# B5PLMF_MAR_HF_B9.net
KiCad netlist of a schematic drawn in Altium Designer
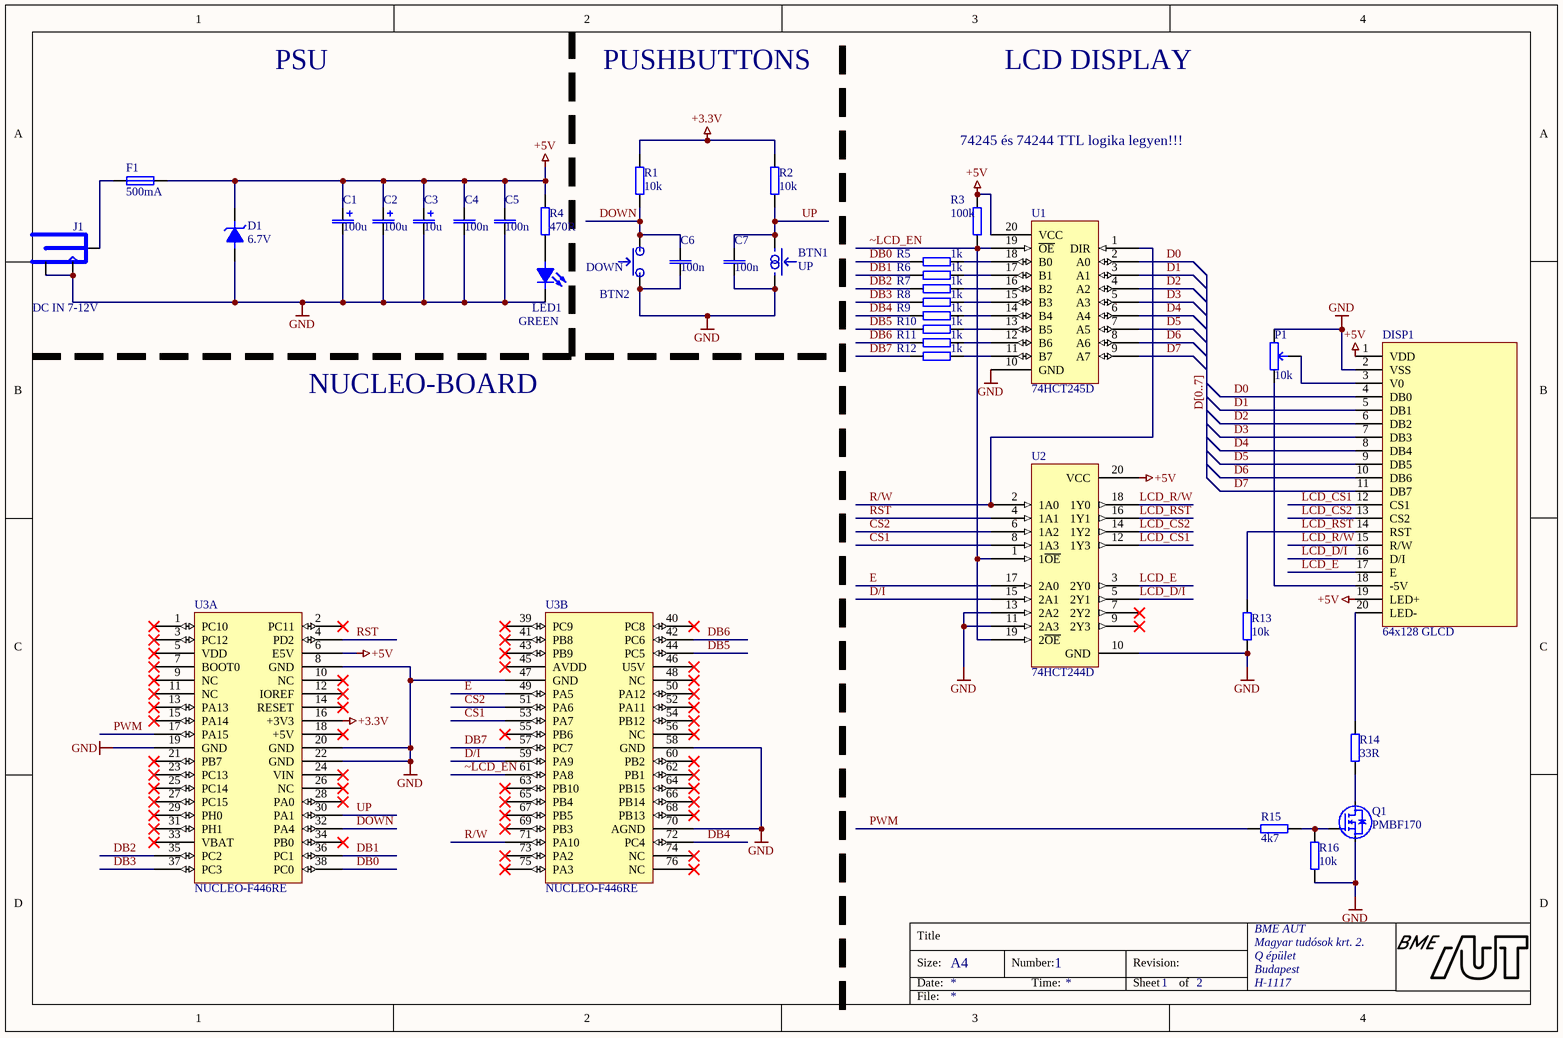
[diagram p0: B5PLMF_MAR_HF_B9.SchDoc]

(export (version "E")
  (design (tool "Eeschema 10.0.6"))
  (components
    (comp (ref "BTN1")
      (value "UP")
      (footprint "PBUTTON_SMD")
      (description "Tactile push button")
      (libsource (lib "SCH_LIB") (part "PUSHBUTTON"))
    )
    (comp (ref "BTN2")
      (value "DOWN")
      (footprint "PBUTTON_SMD")
      (description "Tactile push button")
      (libsource (lib "SCH_LIB") (part "PUSHBUTTON"))
    )
    (comp (ref "C1")
      (value "100u")
      (footprint "D8 ELKO")
      (description "POLARIZED CAPACITOR")
      (libsource (lib "SCH_LIB") (part "CAP_POL"))
    )
    (comp (ref "C2")
      (value "100u")
      (footprint "D8 ELKO")
      (description "POLARIZED CAPACITOR")
      (libsource (lib "SCH_LIB") (part "CAP_POL"))
    )
    (comp (ref "C3")
      (value "10u")
      (footprint "CAP 1210")
      (description "POLARIZED CAPACITOR")
      (libsource (lib "SCH_LIB") (part "CAP_POL"))
    )
    (comp (ref "C4")
      (value "100n")
      (footprint "CAP 0805")
      (description "NON POLARIZED CAPACITOR")
      (libsource (lib "SCH_LIB") (part "CAP"))
    )
    (comp (ref "C5")
      (value "100n")
      (footprint "CAP 0805")
      (description "NON POLARIZED CAPACITOR")
      (libsource (lib "SCH_LIB") (part "CAP"))
    )
    (comp (ref "C6")
      (value "100n")
      (footprint "CAP 0805")
      (description "NON POLARIZED CAPACITOR")
      (libsource (lib "SCH_LIB") (part "CAP"))
    )
    (comp (ref "C7")
      (value "100n")
      (footprint "CAP 0805")
      (description "NON POLARIZED CAPACITOR")
      (libsource (lib "SCH_LIB") (part "CAP"))
    )
    (comp (ref "D1")
      (value "6.7V")
      (footprint "DO-214AC")
      (description "SUPRESSOR DIODE")
      (libsource (lib "SCH_LIB") (part "SUPRESSOR DIODE"))
    )
    (comp (ref "DISP1")
      (value "64x128 GLCD")
      (footprint "64128Q")
      (description "64x128 pixel graphical LCD display from Displaytech")
      (libsource (lib "SCH_LIB") (part "64128QCCBW-3LP"))
    )
    (comp (ref "F1")
      (value "500mA")
      (footprint "FUSE1812")
      (description "FUSE")
      (libsource (lib "SCH_LIB") (part "FUSE"))
    )
    (comp (ref "J1")
      (value "DC IN 7-12V")
      (footprint "DC POWER CONNECTOR")
      (description "DC POWER CONNECTOR 5.5/2.1/9.5mm")
      (libsource (lib "SCH_LIB") (part "DC POWER CONN"))
    )
    (comp (ref "LED1")
      (value "GREEN")
      (footprint "LED 0805G")
      (description "LED")
      (libsource (lib "SCH_LIB") (part "LED"))
    )
    (comp (ref "P1")
      (value "10k")
      (footprint "PT10")
      (description "RESISTOR")
      (libsource (lib "SCH_LIB") (part "POT"))
    )
    (comp (ref "Q1")
      (value "PMBF170")
      (footprint "SOT23")
      (description "N-Channel MOSFET")
      (libsource (lib "SCH_LIB") (part "PMBF170"))
    )
    (comp (ref "R1")
      (value "10k")
      (footprint "RES 0805")
      (description "RESISTOR")
      (libsource (lib "") (part "RES_1"))
    )
    (comp (ref "R2")
      (value "10k")
      (footprint "RES 0805")
      (description "RESISTOR")
      (libsource (lib "") (part "RES_1"))
    )
    (comp (ref "R3")
      (value "100k")
      (footprint "RES 0805")
      (description "RESISTOR")
      (libsource (lib "") (part "RES_1"))
    )
    (comp (ref "R4")
      (value "470R")
      (footprint "RES 0805")
      (description "RESISTOR")
      (libsource (lib "") (part "RES_1"))
    )
    (comp (ref "R5")
      (value "1k")
      (footprint "RES 0805")
      (description "RESISTOR")
      (libsource (lib "SCH_LIB") (part "RES"))
    )
    (comp (ref "R6")
      (value "1k")
      (footprint "RES 0805")
      (description "RESISTOR")
      (libsource (lib "SCH_LIB") (part "RES"))
    )
    (comp (ref "R7")
      (value "1k")
      (footprint "RES 0805")
      (description "RESISTOR")
      (libsource (lib "SCH_LIB") (part "RES"))
    )
    (comp (ref "R8")
      (value "1k")
      (footprint "RES 0805")
      (description "RESISTOR")
      (libsource (lib "SCH_LIB") (part "RES"))
    )
    (comp (ref "R9")
      (value "1k")
      (footprint "RES 0805")
      (description "RESISTOR")
      (libsource (lib "SCH_LIB") (part "RES"))
    )
    (comp (ref "R10")
      (value "1k")
      (footprint "RES 0805")
      (description "RESISTOR")
      (libsource (lib "SCH_LIB") (part "RES"))
    )
    (comp (ref "R11")
      (value "1k")
      (footprint "RES 0805")
      (description "RESISTOR")
      (libsource (lib "SCH_LIB") (part "RES"))
    )
    (comp (ref "R12")
      (value "1k")
      (footprint "RES 0805")
      (description "RESISTOR")
      (libsource (lib "SCH_LIB") (part "RES"))
    )
    (comp (ref "R13")
      (value "10k")
      (footprint "RES 0805")
      (description "RESISTOR")
      (libsource (lib "") (part "RES_1"))
    )
    (comp (ref "R14")
      (value "33R")
      (footprint "RES 0805")
      (description "RESISTOR")
      (libsource (lib "") (part "RES_1"))
    )
    (comp (ref "R15")
      (value "4k7")
      (footprint "RES 0805")
      (description "RESISTOR")
      (libsource (lib "SCH_LIB") (part "RES"))
    )
    (comp (ref "R16")
      (value "10k")
      (footprint "RES 0805")
      (description "RESISTOR")
      (libsource (lib "") (part "RES_1"))
    )
    (comp (ref "U1")
      (value "74HCT245D")
      (footprint "SO20")
      (description "8x Bidirectional bus transciever")
      (libsource (lib "SCH_LIB") (part "74HCT245"))
    )
    (comp (ref "U2")
      (value "74HCT244D")
      (footprint "SO20")
      (description "8xBuffer/Line Driver")
      (libsource (lib "SCH_LIB") (part "74HCT244D"))
    )
    (comp (ref "U3")
      (value "NUCLEO-F446RE")
      (footprint "STM32F4xx_Nucleo")
      (description "STM32F4xx Nucleo board")
      (libsource (lib "SCH_LIB") (part "NUCLEO-F446RE"))
    )
  )
  (nets
    (net (code "1") (name "+3.3V") (class "Default")
      (node (ref "R1") (pin "2") (pinfunction "2_2") (pintype "passive"))
      (node (ref "R2") (pin "2") (pinfunction "2_2") (pintype "passive"))
      (node (ref "U3") (pin "16") (pinfunction "+3V3_16") (pintype "power_in"))
    )
    (net (code "2") (name "+5V") (class "Default")
      (node (ref "C1") (pin "1") (pinfunction "+_1") (pintype "passive"))
      (node (ref "C2") (pin "1") (pinfunction "+_1") (pintype "passive"))
      (node (ref "C3") (pin "1") (pinfunction "+_1") (pintype "passive"))
      (node (ref "C4") (pin "2") (pinfunction "2_2") (pintype "passive"))
      (node (ref "C5") (pin "2") (pinfunction "2_2") (pintype "passive"))
      (node (ref "D1") (pin "2") (pinfunction "K_2") (pintype "passive"))
      (node (ref "DISP1") (pin "1") (pinfunction "VDD_1") (pintype "passive"))
      (node (ref "DISP1") (pin "19") (pinfunction "LED+_19") (pintype "passive"))
      (node (ref "F1") (pin "2") (pinfunction "2_2") (pintype "passive"))
      (node (ref "R3") (pin "2") (pinfunction "2_2") (pintype "passive"))
      (node (ref "R4") (pin "2") (pinfunction "2_2") (pintype "passive"))
      (node (ref "U1") (pin "20") (pinfunction "VCC_20") (pintype "power_in"))
      (node (ref "U2") (pin "20") (pinfunction "VCC_20") (pintype "power_in"))
      (node (ref "U3") (pin "6") (pinfunction "E5V_6") (pintype "power_in"))
    )
    (net (code "3") (name "/CS1") (class "Default")
      (node (ref "U2") (pin "8") (pinfunction "1A3_8") (pintype "input"))
      (node (ref "U3") (pin "53") (pinfunction "PA7_53") (pintype "bidirectional"))
    )
    (net (code "4") (name "/CS2") (class "Default")
      (node (ref "U2") (pin "6") (pinfunction "1A2_6") (pintype "input"))
      (node (ref "U3") (pin "51") (pinfunction "PA6_51") (pintype "bidirectional"))
    )
    (net (code "5") (name "/D0") (class "Default")
      (node (ref "DISP1") (pin "4") (pinfunction "DB0_4") (pintype "passive"))
      (node (ref "U1") (pin "2") (pinfunction "A0_2") (pintype "bidirectional"))
    )
    (net (code "6") (name "/D1") (class "Default")
      (node (ref "DISP1") (pin "5") (pinfunction "DB1_5") (pintype "passive"))
      (node (ref "U1") (pin "3") (pinfunction "A1_3") (pintype "bidirectional"))
    )
    (net (code "7") (name "/D2") (class "Default")
      (node (ref "DISP1") (pin "6") (pinfunction "DB2_6") (pintype "passive"))
      (node (ref "U1") (pin "4") (pinfunction "A2_4") (pintype "bidirectional"))
    )
    (net (code "8") (name "/D3") (class "Default")
      (node (ref "DISP1") (pin "7") (pinfunction "DB3_7") (pintype "passive"))
      (node (ref "U1") (pin "5") (pinfunction "A3_5") (pintype "bidirectional"))
    )
    (net (code "9") (name "/D4") (class "Default")
      (node (ref "DISP1") (pin "8") (pinfunction "DB4_8") (pintype "passive"))
      (node (ref "U1") (pin "6") (pinfunction "A4_6") (pintype "bidirectional"))
    )
    (net (code "10") (name "/D5") (class "Default")
      (node (ref "DISP1") (pin "9") (pinfunction "DB5_9") (pintype "passive"))
      (node (ref "U1") (pin "7") (pinfunction "A5_7") (pintype "bidirectional"))
    )
    (net (code "11") (name "/D6") (class "Default")
      (node (ref "DISP1") (pin "10") (pinfunction "DB6_10") (pintype "passive"))
      (node (ref "U1") (pin "8") (pinfunction "A6_8") (pintype "bidirectional"))
    )
    (net (code "12") (name "/D7") (class "Default")
      (node (ref "DISP1") (pin "11") (pinfunction "DB7_11") (pintype "passive"))
      (node (ref "U1") (pin "9") (pinfunction "A7_9") (pintype "bidirectional"))
    )
    (net (code "13") (name "/DB0") (class "Default")
      (node (ref "R5") (pin "2") (pinfunction "2_2") (pintype "passive"))
      (node (ref "U3") (pin "38") (pinfunction "PC0_38") (pintype "bidirectional"))
    )
    (net (code "14") (name "/DB1") (class "Default")
      (node (ref "R6") (pin "2") (pinfunction "2_2") (pintype "passive"))
      (node (ref "U3") (pin "36") (pinfunction "PC1_36") (pintype "bidirectional"))
    )
    (net (code "15") (name "/DB2") (class "Default")
      (node (ref "R7") (pin "2") (pinfunction "2_2") (pintype "passive"))
      (node (ref "U3") (pin "35") (pinfunction "PC2_35") (pintype "bidirectional"))
    )
    (net (code "16") (name "/DB3") (class "Default")
      (node (ref "R8") (pin "2") (pinfunction "2_2") (pintype "passive"))
      (node (ref "U3") (pin "37") (pinfunction "PC3_37") (pintype "bidirectional"))
    )
    (net (code "17") (name "/DB4") (class "Default")
      (node (ref "R9") (pin "2") (pinfunction "2_2") (pintype "passive"))
      (node (ref "U3") (pin "72") (pinfunction "PC4_72") (pintype "bidirectional"))
    )
    (net (code "18") (name "/DB5") (class "Default")
      (node (ref "R10") (pin "2") (pinfunction "2_2") (pintype "passive"))
      (node (ref "U3") (pin "44") (pinfunction "PC5_44") (pintype "bidirectional"))
    )
    (net (code "19") (name "/DB6") (class "Default")
      (node (ref "R11") (pin "2") (pinfunction "2_2") (pintype "passive"))
      (node (ref "U3") (pin "42") (pinfunction "PC6_42") (pintype "bidirectional"))
    )
    (net (code "20") (name "/DB7") (class "Default")
      (node (ref "R12") (pin "2") (pinfunction "2_2") (pintype "passive"))
      (node (ref "U3") (pin "57") (pinfunction "PC7_57") (pintype "bidirectional"))
    )
    (net (code "21") (name "/DOWN") (class "Default")
      (node (ref "BTN2") (pin "2") (pinfunction "2_2") (pintype "passive"))
      (node (ref "C6") (pin "2") (pinfunction "2_2") (pintype "passive"))
      (node (ref "R1") (pin "1") (pinfunction "1_1") (pintype "passive"))
      (node (ref "U3") (pin "32") (pinfunction "PA4_32") (pintype "bidirectional"))
    )
    (net (code "23") (name "/D{slash}I") (class "Default")
      (node (ref "U2") (pin "15") (pinfunction "2A1_15") (pintype "input"))
      (node (ref "U3") (pin "59") (pinfunction "PA9_59") (pintype "bidirectional"))
    )
    (net (code "24") (name "/E") (class "Default")
      (node (ref "U2") (pin "17") (pinfunction "2A0_17") (pintype "input"))
      (node (ref "U3") (pin "49") (pinfunction "PA5_49") (pintype "bidirectional"))
    )
    (net (code "25") (name "/LCD_CS1") (class "Default")
      (node (ref "DISP1") (pin "12") (pinfunction "CS1_12") (pintype "passive"))
      (node (ref "U2") (pin "12") (pinfunction "1Y3_12") (pintype "output"))
    )
    (net (code "26") (name "/LCD_CS2") (class "Default")
      (node (ref "DISP1") (pin "13") (pinfunction "CS2_13") (pintype "passive"))
      (node (ref "U2") (pin "14") (pinfunction "1Y2_14") (pintype "output"))
    )
    (net (code "27") (name "/LCD_D{slash}I") (class "Default")
      (node (ref "DISP1") (pin "16") (pinfunction "D/I_16") (pintype "passive"))
      (node (ref "U2") (pin "5") (pinfunction "2Y1_5") (pintype "output"))
    )
    (net (code "28") (name "/LCD_E") (class "Default")
      (node (ref "DISP1") (pin "17") (pinfunction "E_17") (pintype "passive"))
      (node (ref "U2") (pin "3") (pinfunction "2Y0_3") (pintype "output"))
    )
    (net (code "29") (name "/LCD_RST") (class "Default")
      (node (ref "DISP1") (pin "14") (pinfunction "RST_14") (pintype "passive"))
      (node (ref "R13") (pin "2") (pinfunction "2_2") (pintype "passive"))
      (node (ref "U2") (pin "16") (pinfunction "1Y1_16") (pintype "output"))
    )
    (net (code "30") (name "/LCD_R{slash}W") (class "Default")
      (node (ref "DISP1") (pin "15") (pinfunction "R/W_15") (pintype "passive"))
      (node (ref "U2") (pin "18") (pinfunction "1Y0_18") (pintype "output"))
    )
    (net (code "31") (name "/PWM") (class "Default")
      (node (ref "R15") (pin "2") (pinfunction "2_2") (pintype "passive"))
      (node (ref "U3") (pin "17") (pinfunction "PA15_17") (pintype "bidirectional"))
    )
    (net (code "32") (name "/RST") (class "Default")
      (node (ref "U2") (pin "4") (pinfunction "1A1_4") (pintype "input"))
      (node (ref "U3") (pin "4") (pinfunction "PD2_4") (pintype "bidirectional"))
    )
    (net (code "33") (name "/R{slash}W") (class "Default")
      (node (ref "U1") (pin "1") (pinfunction "DIR_1") (pintype "input"))
      (node (ref "U2") (pin "2") (pinfunction "1A0_2") (pintype "input"))
      (node (ref "U3") (pin "71") (pinfunction "PA10_71") (pintype "bidirectional"))
    )
    (net (code "34") (name "/UP") (class "Default")
      (node (ref "BTN1") (pin "2") (pinfunction "2_2") (pintype "passive"))
      (node (ref "C7") (pin "2") (pinfunction "2_2") (pintype "passive"))
      (node (ref "R2") (pin "1") (pinfunction "1_1") (pintype "passive"))
      (node (ref "U3") (pin "30") (pinfunction "PA1_30") (pintype "bidirectional"))
    )
    (net (code "35") (name "/~LCD_EN") (class "Default")
      (node (ref "R3") (pin "1") (pinfunction "1_1") (pintype "passive"))
      (node (ref "U1") (pin "19") (pinfunction "~{OE}_19") (pintype "input"))
      (node (ref "U2") (pin "1") (pinfunction "1~{OE}_1") (pintype "input"))
      (node (ref "U2") (pin "19") (pinfunction "2~{OE}_19") (pintype "input"))
      (node (ref "U3") (pin "61") (pinfunction "PA8_61") (pintype "bidirectional"))
    )
    (net (code "36") (name "GND") (class "Default")
      (node (ref "BTN1") (pin "1") (pinfunction "1_1") (pintype "passive"))
      (node (ref "BTN2") (pin "1") (pinfunction "1_1") (pintype "passive"))
      (node (ref "C1") (pin "2") (pinfunction "-_2") (pintype "passive"))
      (node (ref "C2") (pin "2") (pinfunction "-_2") (pintype "passive"))
      (node (ref "C3") (pin "2") (pinfunction "-_2") (pintype "passive"))
      (node (ref "C4") (pin "1") (pinfunction "1_1") (pintype "passive"))
      (node (ref "C5") (pin "1") (pinfunction "1_1") (pintype "passive"))
      (node (ref "C6") (pin "1") (pinfunction "1_1") (pintype "passive"))
      (node (ref "C7") (pin "1") (pinfunction "1_1") (pintype "passive"))
      (node (ref "D1") (pin "1") (pinfunction "A_1") (pintype "passive"))
      (node (ref "DISP1") (pin "2") (pinfunction "VSS_2") (pintype "passive"))
      (node (ref "J1") (pin "2") (pinfunction "GND_2") (pintype "power_in"))
      (node (ref "J1") (pin "3") (pinfunction "GND_3") (pintype "power_in"))
      (node (ref "LED1") (pin "2") (pinfunction "K_2") (pintype "passive"))
      (node (ref "P1") (pin "2") (pinfunction "2_2") (pintype "passive"))
      (node (ref "Q1") (pin "2") (pinfunction "S_2") (pintype "passive"))
      (node (ref "R13") (pin "1") (pinfunction "1_1") (pintype "passive"))
      (node (ref "R16") (pin "1") (pinfunction "1_1") (pintype "passive"))
      (node (ref "U1") (pin "10") (pinfunction "GND_10") (pintype "power_in"))
      (node (ref "U2") (pin "10") (pinfunction "GND_10") (pintype "power_in"))
      (node (ref "U2") (pin "11") (pinfunction "2A3_11") (pintype "input"))
      (node (ref "U2") (pin "13") (pinfunction "2A2_13") (pintype "input"))
      (node (ref "U3") (pin "19") (pinfunction "GND_19") (pintype "passive"))
      (node (ref "U3") (pin "20") (pinfunction "GND_20") (pintype "passive"))
      (node (ref "U3") (pin "22") (pinfunction "GND_22") (pintype "passive"))
      (node (ref "U3") (pin "47") (pinfunction "GND_47") (pintype "passive"))
      (node (ref "U3") (pin "58") (pinfunction "GND_58") (pintype "passive"))
      (node (ref "U3") (pin "70") (pinfunction "AGND_70") (pintype "passive"))
      (node (ref "U3") (pin "8") (pinfunction "GND_8") (pintype "passive"))
    )
    (net (code "37") (name "Net-(DISP1--5V)") (class "Default")
      (node (ref "DISP1") (pin "18") (pinfunction "-5V_18") (pintype "passive"))
      (node (ref "P1") (pin "1") (pinfunction "1_1") (pintype "passive"))
    )
    (net (code "38") (name "Net-(DISP1-LED-)") (class "Default")
      (node (ref "DISP1") (pin "20") (pinfunction "LED-_20") (pintype "passive"))
      (node (ref "R14") (pin "2") (pinfunction "2_2") (pintype "passive"))
    )
    (net (code "39") (name "Net-(DISP1-V0)") (class "Default")
      (node (ref "DISP1") (pin "3") (pinfunction "V0_3") (pintype "passive"))
      (node (ref "P1") (pin "3") (pinfunction "3_3") (pintype "passive"))
    )
    (net (code "40") (name "Net-(J1-9V)") (class "Default")
      (node (ref "F1") (pin "1") (pinfunction "2_1") (pintype "passive"))
      (node (ref "J1") (pin "1") (pinfunction "9V_1") (pintype "power_in"))
    )
    (net (code "41") (name "Net-(LED1-A)") (class "Default")
      (node (ref "LED1") (pin "1") (pinfunction "A_1") (pintype "passive"))
      (node (ref "R4") (pin "1") (pinfunction "1_1") (pintype "passive"))
    )
    (net (code "42") (name "Net-(Q1-D)") (class "Default")
      (node (ref "Q1") (pin "3") (pinfunction "D_3") (pintype "passive"))
      (node (ref "R14") (pin "1") (pinfunction "1_1") (pintype "passive"))
    )
    (net (code "43") (name "Net-(Q1-G)") (class "Default")
      (node (ref "Q1") (pin "1") (pinfunction "G_1") (pintype "passive"))
      (node (ref "R15") (pin "1") (pinfunction "1_1") (pintype "passive"))
      (node (ref "R16") (pin "2") (pinfunction "2_2") (pintype "passive"))
    )
    (net (code "44") (name "Net-(U1-B0)") (class "Default")
      (node (ref "R5") (pin "1") (pinfunction "1_1") (pintype "passive"))
      (node (ref "U1") (pin "18") (pinfunction "B0_18") (pintype "bidirectional"))
    )
    (net (code "45") (name "Net-(U1-B1)") (class "Default")
      (node (ref "R6") (pin "1") (pinfunction "1_1") (pintype "passive"))
      (node (ref "U1") (pin "17") (pinfunction "B1_17") (pintype "bidirectional"))
    )
    (net (code "46") (name "Net-(U1-B2)") (class "Default")
      (node (ref "R7") (pin "1") (pinfunction "1_1") (pintype "passive"))
      (node (ref "U1") (pin "16") (pinfunction "B2_16") (pintype "bidirectional"))
    )
    (net (code "47") (name "Net-(U1-B3)") (class "Default")
      (node (ref "R8") (pin "1") (pinfunction "1_1") (pintype "passive"))
      (node (ref "U1") (pin "15") (pinfunction "B3_15") (pintype "bidirectional"))
    )
    (net (code "48") (name "Net-(U1-B4)") (class "Default")
      (node (ref "R9") (pin "1") (pinfunction "1_1") (pintype "passive"))
      (node (ref "U1") (pin "14") (pinfunction "B4_14") (pintype "bidirectional"))
    )
    (net (code "49") (name "Net-(U1-B5)") (class "Default")
      (node (ref "R10") (pin "1") (pinfunction "1_1") (pintype "passive"))
      (node (ref "U1") (pin "13") (pinfunction "B5_13") (pintype "bidirectional"))
    )
    (net (code "50") (name "Net-(U1-B6)") (class "Default")
      (node (ref "R11") (pin "1") (pinfunction "1_1") (pintype "passive"))
      (node (ref "U1") (pin "12") (pinfunction "B6_12") (pintype "bidirectional"))
    )
    (net (code "51") (name "Net-(U1-B7)") (class "Default")
      (node (ref "R12") (pin "1") (pinfunction "1_1") (pintype "passive"))
      (node (ref "U1") (pin "11") (pinfunction "B7_11") (pintype "bidirectional"))
    )
    (net (code "52") (name "unconnected-(U2-2Y2-Pad7)") (class "Default")
      (node (ref "U2") (pin "7") (pinfunction "2Y2_7") (pintype "output+no_connect"))
    )
    (net (code "53") (name "unconnected-(U2-2Y3-Pad9)") (class "Default")
      (node (ref "U2") (pin "9") (pinfunction "2Y3_9") (pintype "output+no_connect"))
    )
    (net (code "54") (name "unconnected-(U3A-+5V-Pad18)") (class "Default")
      (node (ref "U3") (pin "18") (pinfunction "+5V_18") (pintype "power_in+no_connect"))
    )
    (net (code "55") (name "unconnected-(U3A-BOOT0-Pad7)") (class "Default")
      (node (ref "U3") (pin "7") (pinfunction "BOOT0_7") (pintype "passive+no_connect"))
    )
    (net (code "56") (name "unconnected-(U3A-IOREF-Pad12)") (class "Default")
      (node (ref "U3") (pin "12") (pinfunction "IOREF_12") (pintype "passive+no_connect"))
    )
    (net (code "57") (name "unconnected-(U3A-NC-Pad9)") (class "Default")
      (node (ref "U3") (pin "9") (pinfunction "NC_9") (pintype "passive+no_connect"))
    )
    (net (code "58") (name "unconnected-(U3A-NC-Pad10)") (class "Default")
      (node (ref "U3") (pin "10") (pinfunction "NC_10") (pintype "passive+no_connect"))
    )
    (net (code "59") (name "unconnected-(U3A-NC-Pad11)") (class "Default")
      (node (ref "U3") (pin "11") (pinfunction "NC_11") (pintype "passive+no_connect"))
    )
    (net (code "60") (name "unconnected-(U3A-NC-Pad26)") (class "Default")
      (node (ref "U3") (pin "26") (pinfunction "NC_26") (pintype "passive+no_connect"))
    )
    (net (code "61") (name "unconnected-(U3A-PA0-Pad28)") (class "Default")
      (node (ref "U3") (pin "28") (pinfunction "PA0_28") (pintype "bidirectional+no_connect"))
    )
    (net (code "62") (name "unconnected-(U3A-PA13-Pad13)") (class "Default")
      (node (ref "U3") (pin "13") (pinfunction "PA13_13") (pintype "bidirectional+no_connect"))
    )
    (net (code "63") (name "unconnected-(U3A-PA14-Pad15)") (class "Default")
      (node (ref "U3") (pin "15") (pinfunction "PA14_15") (pintype "bidirectional+no_connect"))
    )
    (net (code "64") (name "unconnected-(U3A-PB0-Pad34)") (class "Default")
      (node (ref "U3") (pin "34") (pinfunction "PB0_34") (pintype "bidirectional+no_connect"))
    )
    (net (code "65") (name "unconnected-(U3A-PB7-Pad21)") (class "Default")
      (node (ref "U3") (pin "21") (pinfunction "PB7_21") (pintype "bidirectional+no_connect"))
    )
    (net (code "66") (name "unconnected-(U3A-PC10-Pad1)") (class "Default")
      (node (ref "U3") (pin "1") (pinfunction "PC10_1") (pintype "bidirectional+no_connect"))
    )
    (net (code "67") (name "unconnected-(U3A-PC11-Pad2)") (class "Default")
      (node (ref "U3") (pin "2") (pinfunction "PC11_2") (pintype "bidirectional+no_connect"))
    )
    (net (code "68") (name "unconnected-(U3A-PC12-Pad3)") (class "Default")
      (node (ref "U3") (pin "3") (pinfunction "PC12_3") (pintype "bidirectional+no_connect"))
    )
    (net (code "69") (name "unconnected-(U3A-PC13-Pad23)") (class "Default")
      (node (ref "U3") (pin "23") (pinfunction "PC13_23") (pintype "bidirectional+no_connect"))
    )
    (net (code "70") (name "unconnected-(U3A-PC14-Pad25)") (class "Default")
      (node (ref "U3") (pin "25") (pinfunction "PC14_25") (pintype "bidirectional+no_connect"))
    )
    (net (code "71") (name "unconnected-(U3A-PC15-Pad27)") (class "Default")
      (node (ref "U3") (pin "27") (pinfunction "PC15_27") (pintype "bidirectional+no_connect"))
    )
    (net (code "72") (name "unconnected-(U3A-PH0-Pad29)") (class "Default")
      (node (ref "U3") (pin "29") (pinfunction "PH0_29") (pintype "bidirectional+no_connect"))
    )
    (net (code "73") (name "unconnected-(U3A-PH1-Pad31)") (class "Default")
      (node (ref "U3") (pin "31") (pinfunction "PH1_31") (pintype "bidirectional+no_connect"))
    )
    (net (code "74") (name "unconnected-(U3A-RESET-Pad14)") (class "Default")
      (node (ref "U3") (pin "14") (pinfunction "RESET_14") (pintype "passive+no_connect"))
    )
    (net (code "75") (name "unconnected-(U3A-VBAT-Pad33)") (class "Default")
      (node (ref "U3") (pin "33") (pinfunction "VBAT_33") (pintype "power_in+no_connect"))
    )
    (net (code "76") (name "unconnected-(U3A-VDD-Pad5)") (class "Default")
      (node (ref "U3") (pin "5") (pinfunction "VDD_5") (pintype "power_in+no_connect"))
    )
    (net (code "77") (name "unconnected-(U3A-VIN-Pad24)") (class "Default")
      (node (ref "U3") (pin "24") (pinfunction "VIN_24") (pintype "power_in+no_connect"))
    )
    (net (code "78") (name "unconnected-(U3B-AVDD-Pad45)") (class "Default")
      (node (ref "U3") (pin "45") (pinfunction "AVDD_45") (pintype "power_in+no_connect"))
    )
    (net (code "79") (name "unconnected-(U3B-NC-Pad48)") (class "Default")
      (node (ref "U3") (pin "48") (pinfunction "NC_48") (pintype "passive+no_connect"))
    )
    (net (code "80") (name "unconnected-(U3B-NC-Pad56)") (class "Default")
      (node (ref "U3") (pin "56") (pinfunction "NC_56") (pintype "passive+no_connect"))
    )
    (net (code "81") (name "unconnected-(U3B-NC-Pad74)") (class "Default")
      (node (ref "U3") (pin "74") (pinfunction "NC_74") (pintype "passive+no_connect"))
    )
    (net (code "82") (name "unconnected-(U3B-NC-Pad76)") (class "Default")
      (node (ref "U3") (pin "76") (pinfunction "NC_76") (pintype "passive+no_connect"))
    )
    (net (code "83") (name "unconnected-(U3B-PA2-Pad73)") (class "Default")
      (node (ref "U3") (pin "73") (pinfunction "PA2_73") (pintype "bidirectional+no_connect"))
    )
    (net (code "84") (name "unconnected-(U3B-PA3-Pad75)") (class "Default")
      (node (ref "U3") (pin "75") (pinfunction "PA3_75") (pintype "bidirectional+no_connect"))
    )
    (net (code "85") (name "unconnected-(U3B-PA11-Pad52)") (class "Default")
      (node (ref "U3") (pin "52") (pinfunction "PA11_52") (pintype "bidirectional+no_connect"))
    )
    (net (code "86") (name "unconnected-(U3B-PA12-Pad50)") (class "Default")
      (node (ref "U3") (pin "50") (pinfunction "PA12_50") (pintype "bidirectional+no_connect"))
    )
    (net (code "87") (name "unconnected-(U3B-PB1-Pad62)") (class "Default")
      (node (ref "U3") (pin "62") (pinfunction "PB1_62") (pintype "bidirectional+no_connect"))
    )
    (net (code "88") (name "unconnected-(U3B-PB2-Pad60)") (class "Default")
      (node (ref "U3") (pin "60") (pinfunction "PB2_60") (pintype "bidirectional+no_connect"))
    )
    (net (code "89") (name "unconnected-(U3B-PB3-Pad69)") (class "Default")
      (node (ref "U3") (pin "69") (pinfunction "PB3_69") (pintype "bidirectional+no_connect"))
    )
    (net (code "90") (name "unconnected-(U3B-PB4-Pad65)") (class "Default")
      (node (ref "U3") (pin "65") (pinfunction "PB4_65") (pintype "bidirectional+no_connect"))
    )
    (net (code "91") (name "unconnected-(U3B-PB5-Pad67)") (class "Default")
      (node (ref "U3") (pin "67") (pinfunction "PB5_67") (pintype "bidirectional+no_connect"))
    )
    (net (code "92") (name "unconnected-(U3B-PB6-Pad55)") (class "Default")
      (node (ref "U3") (pin "55") (pinfunction "PB6_55") (pintype "bidirectional+no_connect"))
    )
    (net (code "93") (name "unconnected-(U3B-PB8-Pad41)") (class "Default")
      (node (ref "U3") (pin "41") (pinfunction "PB8_41") (pintype "bidirectional+no_connect"))
    )
    (net (code "94") (name "unconnected-(U3B-PB9-Pad43)") (class "Default")
      (node (ref "U3") (pin "43") (pinfunction "PB9_43") (pintype "bidirectional+no_connect"))
    )
    (net (code "95") (name "unconnected-(U3B-PB10-Pad63)") (class "Default")
      (node (ref "U3") (pin "63") (pinfunction "PB10_63") (pintype "bidirectional+no_connect"))
    )
    (net (code "96") (name "unconnected-(U3B-PB12-Pad54)") (class "Default")
      (node (ref "U3") (pin "54") (pinfunction "PB12_54") (pintype "bidirectional+no_connect"))
    )
    (net (code "97") (name "unconnected-(U3B-PB13-Pad68)") (class "Default")
      (node (ref "U3") (pin "68") (pinfunction "PB13_68") (pintype "bidirectional+no_connect"))
    )
    (net (code "98") (name "unconnected-(U3B-PB14-Pad66)") (class "Default")
      (node (ref "U3") (pin "66") (pinfunction "PB14_66") (pintype "bidirectional+no_connect"))
    )
    (net (code "99") (name "unconnected-(U3B-PB15-Pad64)") (class "Default")
      (node (ref "U3") (pin "64") (pinfunction "PB15_64") (pintype "bidirectional+no_connect"))
    )
    (net (code "100") (name "unconnected-(U3B-PC8-Pad40)") (class "Default")
      (node (ref "U3") (pin "40") (pinfunction "PC8_40") (pintype "bidirectional+no_connect"))
    )
    (net (code "101") (name "unconnected-(U3B-PC9-Pad39)") (class "Default")
      (node (ref "U3") (pin "39") (pinfunction "PC9_39") (pintype "bidirectional+no_connect"))
    )
    (net (code "102") (name "unconnected-(U3B-U5V-Pad46)") (class "Default")
      (node (ref "U3") (pin "46") (pinfunction "U5V_46") (pintype "power_in+no_connect"))
    )
  )
)
